# s2.net
KiCad netlist of a schematic drawn in Altium Designer
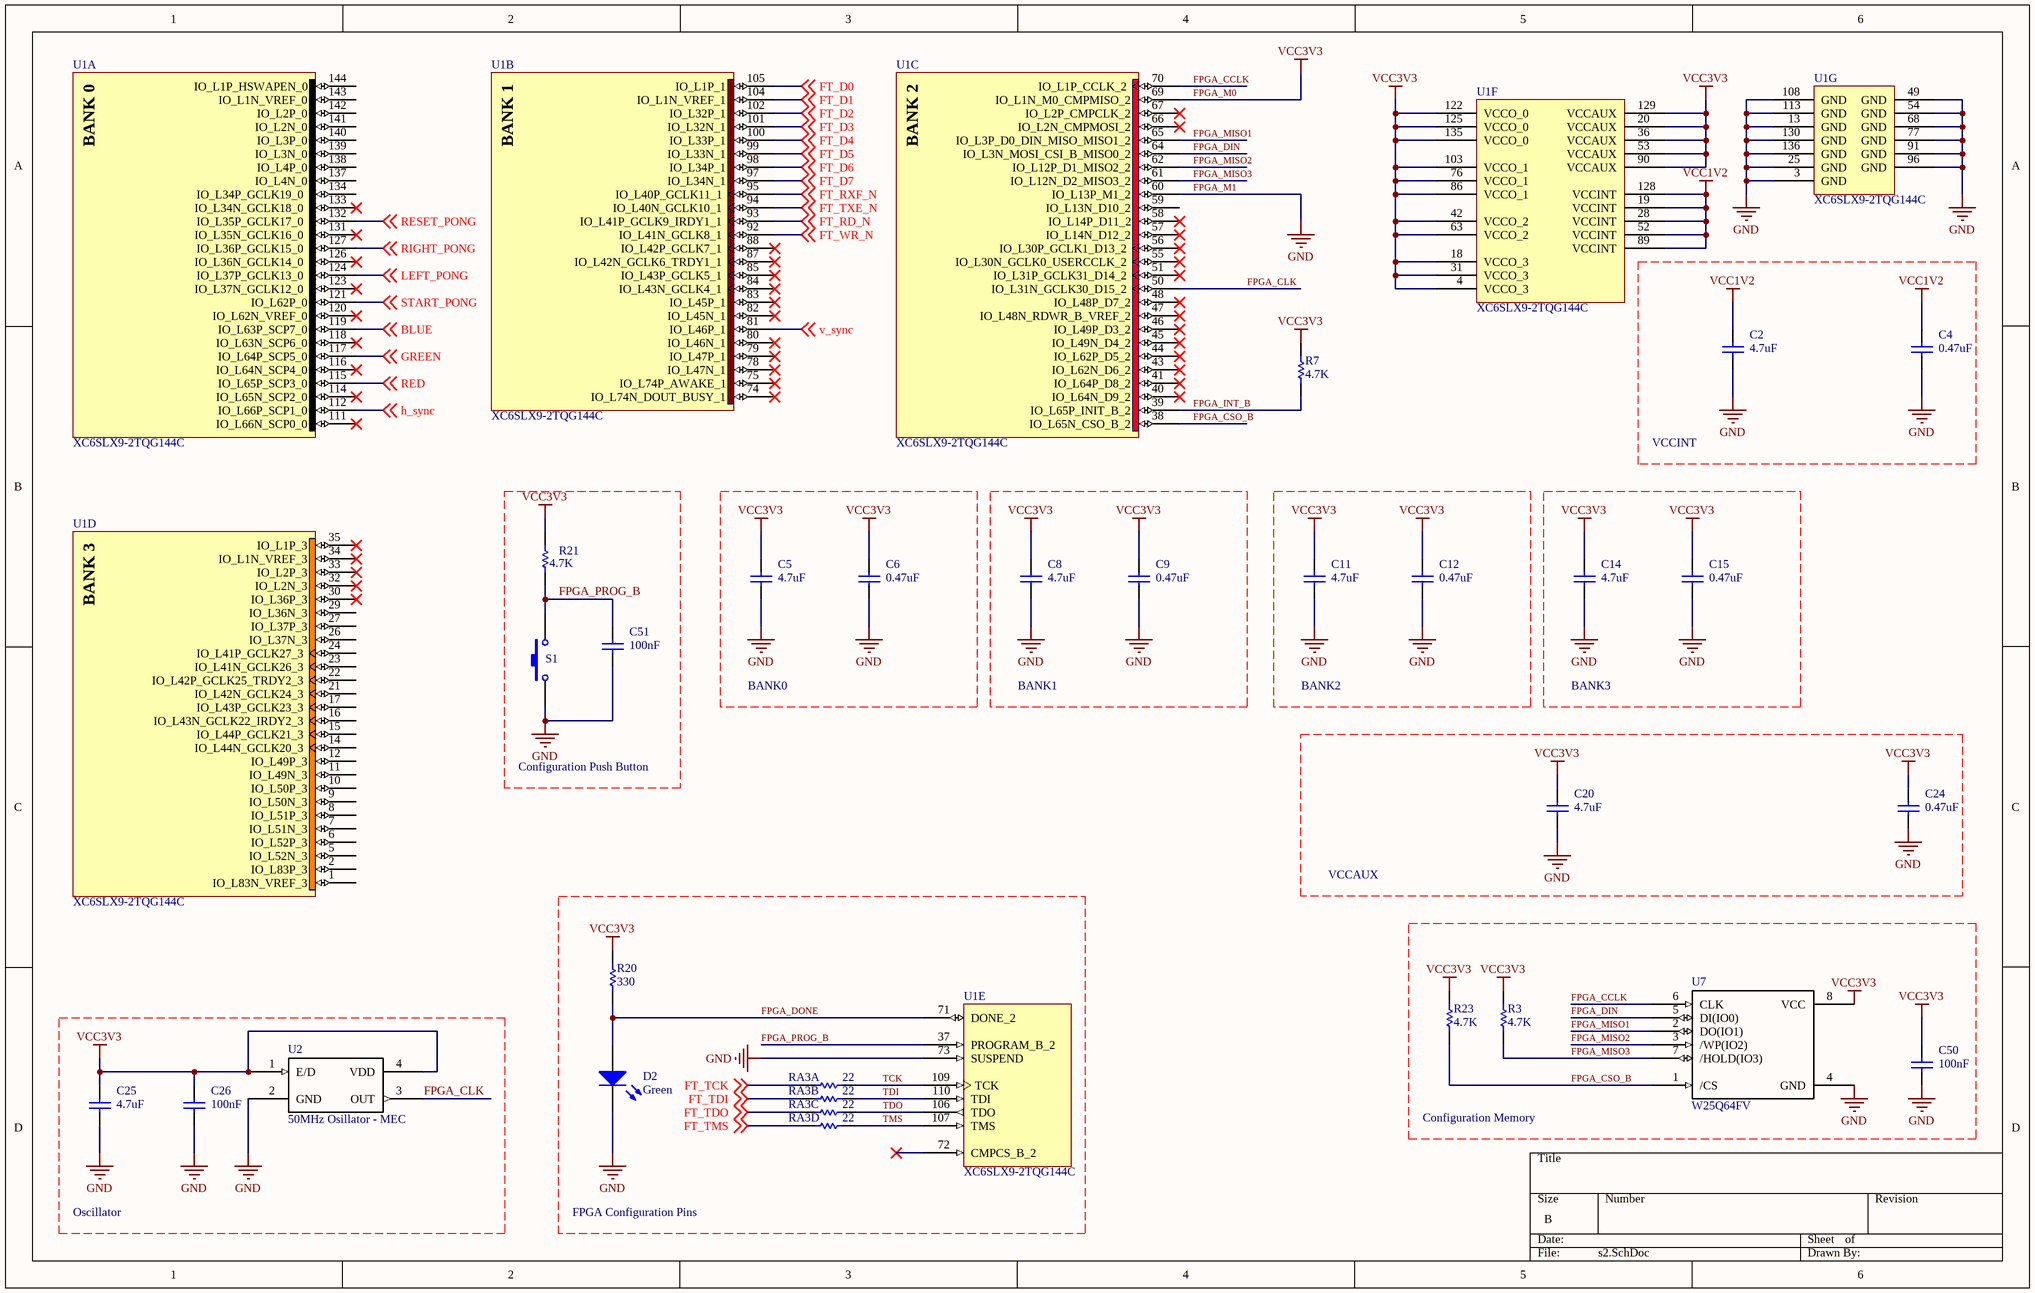
[diagram p0: s2.SchDoc]

(export (version "E")
  (design (tool "Eeschema 10.0.6"))
  (components
    (comp (ref "C2")
      (value "4.7uF")
      (footprint "0805 CAP")
      (description "Capacitor")
      (fields (field (name "Comment") "Cap") (field (name "PUBLISHER") "Altium Limited"))
      (libsource (lib "Miscellaneous Devices") (part "Cap"))
    )
    (comp (ref "C4")
      (value "0.47uF")
      (footprint "0805 CAP")
      (description "Capacitor")
      (fields (field (name "Comment") "Cap") (field (name "PUBLISHER") "Altium Limited"))
      (libsource (lib "Miscellaneous Devices") (part "Cap"))
    )
    (comp (ref "C5")
      (value "4.7uF")
      (footprint "0805 CAP")
      (description "Capacitor")
      (fields (field (name "Comment") "Cap") (field (name "PUBLISHER") "Altium Limited"))
      (libsource (lib "Miscellaneous Devices") (part "Cap"))
    )
    (comp (ref "C6")
      (value "0.47uF")
      (footprint "0805 CAP")
      (description "Capacitor")
      (fields (field (name "Comment") "Cap") (field (name "PUBLISHER") "Altium Limited"))
      (libsource (lib "Miscellaneous Devices") (part "Cap"))
    )
    (comp (ref "C8")
      (value "4.7uF")
      (footprint "0805 CAP")
      (description "Capacitor")
      (fields (field (name "Comment") "Cap") (field (name "PUBLISHER") "Altium Limited"))
      (libsource (lib "Miscellaneous Devices") (part "Cap"))
    )
    (comp (ref "C9")
      (value "0.47uF")
      (footprint "0805 CAP")
      (description "Capacitor")
      (fields (field (name "Comment") "Cap") (field (name "PUBLISHER") "Altium Limited"))
      (libsource (lib "Miscellaneous Devices") (part "Cap"))
    )
    (comp (ref "C11")
      (value "4.7uF")
      (footprint "0805 CAP")
      (description "Capacitor")
      (fields (field (name "Comment") "Cap") (field (name "PUBLISHER") "Altium Limited"))
      (libsource (lib "Miscellaneous Devices") (part "Cap"))
    )
    (comp (ref "C12")
      (value "0.47uF")
      (footprint "0805 CAP")
      (description "Capacitor")
      (fields (field (name "Comment") "Cap") (field (name "PUBLISHER") "Altium Limited"))
      (libsource (lib "Miscellaneous Devices") (part "Cap"))
    )
    (comp (ref "C14")
      (value "4.7uF")
      (footprint "0805 CAP")
      (description "Capacitor")
      (fields (field (name "Comment") "Cap") (field (name "PUBLISHER") "Altium Limited"))
      (libsource (lib "Miscellaneous Devices") (part "Cap"))
    )
    (comp (ref "C15")
      (value "0.47uF")
      (footprint "0805 CAP")
      (description "Capacitor")
      (fields (field (name "Comment") "Cap") (field (name "PUBLISHER") "Altium Limited"))
      (libsource (lib "Miscellaneous Devices") (part "Cap"))
    )
    (comp (ref "C20")
      (value "4.7uF")
      (footprint "0805 CAP")
      (description "Capacitor")
      (fields (field (name "Comment") "Cap") (field (name "PUBLISHER") "Altium Limited"))
      (libsource (lib "Miscellaneous Devices") (part "Cap"))
    )
    (comp (ref "C24")
      (value "0.47uF")
      (footprint "0805 CAP")
      (description "Capacitor")
      (fields (field (name "Comment") "Cap") (field (name "PUBLISHER") "Altium Limited"))
      (libsource (lib "Miscellaneous Devices") (part "Cap"))
    )
    (comp (ref "C25")
      (value "4.7uF")
      (footprint "0805 CAP")
      (description "Capacitor")
      (fields (field (name "Comment") "Cap") (field (name "PUBLISHER") "Altium Limited"))
      (libsource (lib "Miscellaneous Devices") (part "Cap"))
    )
    (comp (ref "C26")
      (value "100nF")
      (footprint "0805 CAP")
      (description "Capacitor")
      (fields (field (name "Comment") "Cap") (field (name "PUBLISHER") "Altium Limited"))
      (libsource (lib "Miscellaneous Devices") (part "Cap"))
    )
    (comp (ref "C50")
      (value "100nF")
      (footprint "0805 CAP")
      (description "Capacitor")
      (fields (field (name "Comment") "Cap") (field (name "PUBLISHER") "Altium Limited"))
      (libsource (lib "Miscellaneous Devices") (part "Cap"))
    )
    (comp (ref "C51")
      (value "100nF")
      (footprint "0805 CAP")
      (description "Capacitor")
      (fields (field (name "Comment") "Cap") (field (name "PUBLISHER") "Altium Limited"))
      (libsource (lib "Miscellaneous Devices") (part "Cap"))
    )
    (comp (ref "D2")
      (value "Green")
      (footprint "0805 LED")
      (description "Typical INFRARED GaAs LED")
      (fields (field (name "PUBLISHER") "Altium Limited"))
      (libsource (lib "Miscellaneous Devices") (part "LED0"))
    )
    (comp (ref "R3")
      (value "4.7K")
      (footprint "0805 RES")
      (description "Resistor")
      (fields (field (name "Comment") "Res1") (field (name "PUBLISHER") "Altium Limited"))
      (libsource (lib "Miscellaneous Devices") (part "Res1"))
    )
    (comp (ref "R7")
      (value "4.7K")
      (footprint "0805 RES")
      (description "Resistor")
      (fields (field (name "Comment") "Res1") (field (name "PUBLISHER") "Altium Limited"))
      (libsource (lib "Miscellaneous Devices") (part "Res1"))
    )
    (comp (ref "R20")
      (value "330")
      (footprint "0805 RES")
      (description "Resistor")
      (fields (field (name "Comment") "Res1") (field (name "PUBLISHER") "Altium Limited"))
      (libsource (lib "Miscellaneous Devices") (part "Res1"))
    )
    (comp (ref "R21")
      (value "4.7K")
      (footprint "0805 RES")
      (description "Resistor")
      (fields (field (name "Comment") "Res1") (field (name "PUBLISHER") "Altium Limited"))
      (libsource (lib "Miscellaneous Devices") (part "Res1"))
    )
    (comp (ref "R23")
      (value "4.7K")
      (footprint "0805 RES")
      (description "Resistor")
      (fields (field (name "Comment") "Res1") (field (name "PUBLISHER") "Altium Limited"))
      (libsource (lib "Miscellaneous Devices") (part "Res1"))
    )
    (comp (ref "RA3A")
      (value "22")
      (footprint "0805 RES")
      (description "Resistor")
      (fields (field (name "Comment") "Res1") (field (name "PUBLISHER") "Altium Limited"))
      (libsource (lib "Miscellaneous Devices") (part "Res1"))
    )
    (comp (ref "RA3B")
      (value "22")
      (footprint "0805 RES")
      (description "Resistor")
      (fields (field (name "Comment") "Res1") (field (name "PUBLISHER") "Altium Limited"))
      (libsource (lib "Miscellaneous Devices") (part "Res1"))
    )
    (comp (ref "RA3C")
      (value "22")
      (footprint "0805 RES")
      (description "Resistor")
      (fields (field (name "Comment") "Res1") (field (name "PUBLISHER") "Altium Limited"))
      (libsource (lib "Miscellaneous Devices") (part "Res1"))
    )
    (comp (ref "RA3D")
      (value "22")
      (footprint "0805 RES")
      (description "Resistor")
      (fields (field (name "Comment") "Res1") (field (name "PUBLISHER") "Altium Limited"))
      (libsource (lib "Miscellaneous Devices") (part "Res1"))
    )
    (comp (ref "S1")
      (value "SW-PB")
      (footprint "Tack Switch")
      (description "Switch")
      (fields (field (name "PUBLISHER") "Altium Limited"))
      (libsource (lib "Miscellaneous Devices") (part "SW-PB"))
    )
    (comp (ref "U1")
      (value "XC6SLX9-2TQG144C")
      (footprint "TQG144_M")
      (libsource (lib "Xilinx Spartan-6") (part "XC6SLX9-2TQG144C"))
    )
    (comp (ref "U2")
      (value "50MHz Osillator - MEC")
      (footprint "50MHz Osillator - MEC")
      (libsource (lib "Schlib1") (part "50MHz Osillator - MEC"))
    )
    (comp (ref "U7")
      (value "W25Q64FV")
      (footprint "SO08 - duplicate")
      (libsource (lib "Schlib1") (part "W25Q64FV"))
    )
  )
  (nets
    (net (code "1") (name "/FPGA_CCLK") (class "Default")
      (node (ref "U1") (pin "70") (pinfunction "IO_L1P_CCLK_2_70") (pintype "bidirectional"))
      (node (ref "U7") (pin "6") (pinfunction "CLK_6") (pintype "input"))
    )
    (net (code "2") (name "/FPGA_CLK") (class "Default")
      (node (ref "U1") (pin "50") (pinfunction "IO_L31N_GCLK30_D15_2_50") (pintype "bidirectional"))
      (node (ref "U2") (pin "3") (pinfunction "OUT_3") (pintype "output"))
    )
    (net (code "3") (name "/FPGA_CSO_B") (class "Default")
      (node (ref "R23") (pin "1") (pinfunction "1_1") (pintype "passive"))
      (node (ref "U1") (pin "38") (pinfunction "IO_L65N_CSO_B_2_38") (pintype "bidirectional"))
      (node (ref "U7") (pin "1") (pinfunction "/CS_1") (pintype "input"))
    )
    (net (code "4") (name "/FPGA_DIN") (class "Default")
      (node (ref "U1") (pin "64") (pinfunction "IO_L3N_MOSI_CSI_B_MISO0_2_64") (pintype "bidirectional"))
      (node (ref "U7") (pin "5") (pinfunction "DI(IO0)_5") (pintype "bidirectional"))
    )
    (net (code "5") (name "/FPGA_DONE") (class "Default")
      (node (ref "D2") (pin "1") (pinfunction "A_1") (pintype "passive"))
      (node (ref "R20") (pin "1") (pinfunction "1_1") (pintype "passive"))
      (node (ref "U1") (pin "71") (pinfunction "DONE_2_71") (pintype "bidirectional"))
    )
    (net (code "6") (name "/FPGA_INT_B") (class "Default")
      (node (ref "R7") (pin "1") (pinfunction "1_1") (pintype "passive"))
      (node (ref "U1") (pin "39") (pinfunction "IO_L65P_INIT_B_2_39") (pintype "bidirectional"))
    )
    (net (code "7") (name "/FPGA_MISO1") (class "Default")
      (node (ref "U1") (pin "65") (pinfunction "IO_L3P_D0_DIN_MISO_MISO1_2_65") (pintype "bidirectional"))
      (node (ref "U7") (pin "2") (pinfunction "DO(IO1)_2") (pintype "bidirectional"))
    )
    (net (code "8") (name "/FPGA_MISO2") (class "Default")
      (node (ref "U1") (pin "62") (pinfunction "IO_L12P_D1_MISO2_2_62") (pintype "bidirectional"))
      (node (ref "U7") (pin "3") (pinfunction "/WP(IO2)_3") (pintype "input"))
    )
    (net (code "9") (name "/FPGA_MISO3") (class "Default")
      (node (ref "R3") (pin "1") (pinfunction "1_1") (pintype "passive"))
      (node (ref "U1") (pin "61") (pinfunction "IO_L12N_D2_MISO3_2_61") (pintype "bidirectional"))
      (node (ref "U7") (pin "7") (pinfunction "/HOLD(IO3)_7") (pintype "bidirectional"))
    )
    (net (code "10") (name "/FPGA_PROG_B") (class "Default")
      (node (ref "C51") (pin "2") (pinfunction "2_2") (pintype "passive"))
      (node (ref "R21") (pin "1") (pinfunction "1_1") (pintype "passive"))
      (node (ref "S1") (pin "2") (pinfunction "2_2") (pintype "passive"))
      (node (ref "U1") (pin "37") (pinfunction "PROGRAM_B_2_37") (pintype "input"))
    )
    (net (code "11") (name "/TCK") (class "Default")
      (node (ref "RA3A") (pin "1") (pinfunction "1_1") (pintype "passive"))
      (node (ref "U1") (pin "109") (pinfunction "TCK_109") (pintype "input"))
    )
    (net (code "12") (name "/TDI") (class "Default")
      (node (ref "RA3B") (pin "1") (pinfunction "1_1") (pintype "passive"))
      (node (ref "U1") (pin "110") (pinfunction "TDI_110") (pintype "input"))
    )
    (net (code "13") (name "/TDO") (class "Default")
      (node (ref "RA3C") (pin "1") (pinfunction "1_1") (pintype "passive"))
      (node (ref "U1") (pin "106") (pinfunction "TDO_106") (pintype "output"))
    )
    (net (code "14") (name "/TMS") (class "Default")
      (node (ref "RA3D") (pin "1") (pinfunction "1_1") (pintype "passive"))
      (node (ref "U1") (pin "107") (pinfunction "TMS_107") (pintype "input"))
    )
    (net (code "15") (name "BLUE") (class "Default")
      (node (ref "U1") (pin "119") (pinfunction "IO_L63P_SCP7_0_119") (pintype "bidirectional"))
    )
    (net (code "16") (name "FT_D0") (class "Default")
      (node (ref "U1") (pin "105") (pinfunction "IO_L1P_1_105") (pintype "bidirectional"))
    )
    (net (code "17") (name "FT_D1") (class "Default")
      (node (ref "U1") (pin "104") (pinfunction "IO_L1N_VREF_1_104") (pintype "bidirectional"))
    )
    (net (code "18") (name "FT_D2") (class "Default")
      (node (ref "U1") (pin "102") (pinfunction "IO_L32P_1_102") (pintype "bidirectional"))
    )
    (net (code "19") (name "FT_D3") (class "Default")
      (node (ref "U1") (pin "101") (pinfunction "IO_L32N_1_101") (pintype "bidirectional"))
    )
    (net (code "20") (name "FT_D4") (class "Default")
      (node (ref "U1") (pin "100") (pinfunction "IO_L33P_1_100") (pintype "bidirectional"))
    )
    (net (code "21") (name "FT_D5") (class "Default")
      (node (ref "U1") (pin "99") (pinfunction "IO_L33N_1_99") (pintype "bidirectional"))
    )
    (net (code "22") (name "FT_D6") (class "Default")
      (node (ref "U1") (pin "98") (pinfunction "IO_L34P_1_98") (pintype "bidirectional"))
    )
    (net (code "23") (name "FT_D7") (class "Default")
      (node (ref "U1") (pin "97") (pinfunction "IO_L34N_1_97") (pintype "bidirectional"))
    )
    (net (code "24") (name "FT_RD_N") (class "Default")
      (node (ref "U1") (pin "93") (pinfunction "IO_L41P_GCLK9_IRDY1_1_93") (pintype "bidirectional"))
    )
    (net (code "25") (name "FT_RXF_N") (class "Default")
      (node (ref "U1") (pin "95") (pinfunction "IO_L40P_GCLK11_1_95") (pintype "bidirectional"))
    )
    (net (code "26") (name "FT_TCK") (class "Default")
      (node (ref "RA3A") (pin "2") (pinfunction "2_2") (pintype "passive"))
    )
    (net (code "27") (name "FT_TDI") (class "Default")
      (node (ref "RA3B") (pin "2") (pinfunction "2_2") (pintype "passive"))
    )
    (net (code "28") (name "FT_TDO") (class "Default")
      (node (ref "RA3C") (pin "2") (pinfunction "2_2") (pintype "passive"))
    )
    (net (code "29") (name "FT_TMS") (class "Default")
      (node (ref "RA3D") (pin "2") (pinfunction "2_2") (pintype "passive"))
    )
    (net (code "30") (name "FT_TXE_N") (class "Default")
      (node (ref "U1") (pin "94") (pinfunction "IO_L40N_GCLK10_1_94") (pintype "bidirectional"))
    )
    (net (code "31") (name "FT_WR_N") (class "Default")
      (node (ref "U1") (pin "92") (pinfunction "IO_L41N_GCLK8_1_92") (pintype "bidirectional"))
    )
    (net (code "32") (name "GND") (class "Default")
      (node (ref "C11") (pin "1") (pinfunction "1_1") (pintype "passive"))
      (node (ref "C12") (pin "1") (pinfunction "1_1") (pintype "passive"))
      (node (ref "C14") (pin "1") (pinfunction "1_1") (pintype "passive"))
      (node (ref "C15") (pin "1") (pinfunction "1_1") (pintype "passive"))
      (node (ref "C2") (pin "1") (pinfunction "1_1") (pintype "passive"))
      (node (ref "C20") (pin "1") (pinfunction "1_1") (pintype "passive"))
      (node (ref "C24") (pin "1") (pinfunction "1_1") (pintype "passive"))
      (node (ref "C25") (pin "1") (pinfunction "1_1") (pintype "passive"))
      (node (ref "C26") (pin "1") (pinfunction "1_1") (pintype "passive"))
      (node (ref "C4") (pin "1") (pinfunction "1_1") (pintype "passive"))
      (node (ref "C5") (pin "1") (pinfunction "1_1") (pintype "passive"))
      (node (ref "C50") (pin "1") (pinfunction "1_1") (pintype "passive"))
      (node (ref "C51") (pin "1") (pinfunction "1_1") (pintype "passive"))
      (node (ref "C6") (pin "1") (pinfunction "1_1") (pintype "passive"))
      (node (ref "C8") (pin "1") (pinfunction "1_1") (pintype "passive"))
      (node (ref "C9") (pin "1") (pinfunction "1_1") (pintype "passive"))
      (node (ref "D2") (pin "2") (pinfunction "K_2") (pintype "passive"))
      (node (ref "S1") (pin "1") (pinfunction "1_1") (pintype "passive"))
      (node (ref "U1") (pin "108") (pinfunction "GND_108") (pintype "power_in"))
      (node (ref "U1") (pin "113") (pinfunction "GND_113") (pintype "power_in"))
      (node (ref "U1") (pin "13") (pinfunction "GND_13") (pintype "power_in"))
      (node (ref "U1") (pin "130") (pinfunction "GND_130") (pintype "power_in"))
      (node (ref "U1") (pin "136") (pinfunction "GND_136") (pintype "power_in"))
      (node (ref "U1") (pin "25") (pinfunction "GND_25") (pintype "power_in"))
      (node (ref "U1") (pin "3") (pinfunction "GND_3") (pintype "power_in"))
      (node (ref "U1") (pin "49") (pinfunction "GND_49") (pintype "power_in"))
      (node (ref "U1") (pin "54") (pinfunction "GND_54") (pintype "power_in"))
      (node (ref "U1") (pin "60") (pinfunction "IO_L13P_M1_2_60") (pintype "bidirectional"))
      (node (ref "U1") (pin "68") (pinfunction "GND_68") (pintype "power_in"))
      (node (ref "U1") (pin "73") (pinfunction "SUSPEND_73") (pintype "input"))
      (node (ref "U1") (pin "77") (pinfunction "GND_77") (pintype "power_in"))
      (node (ref "U1") (pin "91") (pinfunction "GND_91") (pintype "power_in"))
      (node (ref "U1") (pin "96") (pinfunction "GND_96") (pintype "power_in"))
      (node (ref "U2") (pin "2") (pinfunction "GND_2") (pintype "passive"))
      (node (ref "U7") (pin "4") (pinfunction "GND_4") (pintype "passive"))
    )
    (net (code "33") (name "GREEN") (class "Default")
      (node (ref "U1") (pin "117") (pinfunction "IO_L64P_SCP5_0_117") (pintype "bidirectional"))
    )
    (net (code "34") (name "LEFT_PONG") (class "Default")
      (node (ref "U1") (pin "124") (pinfunction "IO_L37P_GCLK13_0_124") (pintype "bidirectional"))
    )
    (net (code "35") (name "RED") (class "Default")
      (node (ref "U1") (pin "115") (pinfunction "IO_L65P_SCP3_0_115") (pintype "bidirectional"))
    )
    (net (code "36") (name "RESET_PONG") (class "Default")
      (node (ref "U1") (pin "132") (pinfunction "IO_L35P_GCLK17_0_132") (pintype "bidirectional"))
    )
    (net (code "37") (name "RIGHT_PONG") (class "Default")
      (node (ref "U1") (pin "127") (pinfunction "IO_L36P_GCLK15_0_127") (pintype "bidirectional"))
    )
    (net (code "38") (name "START_PONG") (class "Default")
      (node (ref "U1") (pin "121") (pinfunction "IO_L62P_0_121") (pintype "bidirectional"))
    )
    (net (code "39") (name "VCC1V2") (class "Default")
      (node (ref "C2") (pin "2") (pinfunction "2_2") (pintype "passive"))
      (node (ref "C4") (pin "2") (pinfunction "2_2") (pintype "passive"))
      (node (ref "U1") (pin "128") (pinfunction "VCCINT_128") (pintype "power_in"))
      (node (ref "U1") (pin "19") (pinfunction "VCCINT_19") (pintype "power_in"))
      (node (ref "U1") (pin "28") (pinfunction "VCCINT_28") (pintype "power_in"))
      (node (ref "U1") (pin "52") (pinfunction "VCCINT_52") (pintype "power_in"))
      (node (ref "U1") (pin "89") (pinfunction "VCCINT_89") (pintype "power_in"))
    )
    (net (code "40") (name "VCC3V3") (class "Default")
      (node (ref "C11") (pin "2") (pinfunction "2_2") (pintype "passive"))
      (node (ref "C12") (pin "2") (pinfunction "2_2") (pintype "passive"))
      (node (ref "C14") (pin "2") (pinfunction "2_2") (pintype "passive"))
      (node (ref "C15") (pin "2") (pinfunction "2_2") (pintype "passive"))
      (node (ref "C20") (pin "2") (pinfunction "2_2") (pintype "passive"))
      (node (ref "C24") (pin "2") (pinfunction "2_2") (pintype "passive"))
      (node (ref "C25") (pin "2") (pinfunction "2_2") (pintype "passive"))
      (node (ref "C26") (pin "2") (pinfunction "2_2") (pintype "passive"))
      (node (ref "C5") (pin "2") (pinfunction "2_2") (pintype "passive"))
      (node (ref "C50") (pin "2") (pinfunction "2_2") (pintype "passive"))
      (node (ref "C6") (pin "2") (pinfunction "2_2") (pintype "passive"))
      (node (ref "C8") (pin "2") (pinfunction "2_2") (pintype "passive"))
      (node (ref "C9") (pin "2") (pinfunction "2_2") (pintype "passive"))
      (node (ref "R20") (pin "2") (pinfunction "2_2") (pintype "passive"))
      (node (ref "R21") (pin "2") (pinfunction "2_2") (pintype "passive"))
      (node (ref "R23") (pin "2") (pinfunction "2_2") (pintype "passive"))
      (node (ref "R3") (pin "2") (pinfunction "2_2") (pintype "passive"))
      (node (ref "R7") (pin "2") (pinfunction "2_2") (pintype "passive"))
      (node (ref "U1") (pin "103") (pinfunction "VCCO_1_103") (pintype "power_in"))
      (node (ref "U1") (pin "122") (pinfunction "VCCO_0_122") (pintype "power_in"))
      (node (ref "U1") (pin "125") (pinfunction "VCCO_0_125") (pintype "power_in"))
      (node (ref "U1") (pin "129") (pinfunction "VCCAUX_129") (pintype "power_in"))
      (node (ref "U1") (pin "135") (pinfunction "VCCO_0_135") (pintype "power_in"))
      (node (ref "U1") (pin "18") (pinfunction "VCCO_3_18") (pintype "power_in"))
      (node (ref "U1") (pin "20") (pinfunction "VCCAUX_20") (pintype "power_in"))
      (node (ref "U1") (pin "31") (pinfunction "VCCO_3_31") (pintype "power_in"))
      (node (ref "U1") (pin "36") (pinfunction "VCCAUX_36") (pintype "power_in"))
      (node (ref "U1") (pin "4") (pinfunction "VCCO_3_4") (pintype "power_in"))
      (node (ref "U1") (pin "42") (pinfunction "VCCO_2_42") (pintype "power_in"))
      (node (ref "U1") (pin "53") (pinfunction "VCCAUX_53") (pintype "power_in"))
      (node (ref "U1") (pin "63") (pinfunction "VCCO_2_63") (pintype "power_in"))
      (node (ref "U1") (pin "69") (pinfunction "IO_L1N_M0_CMPMISO_2_69") (pintype "bidirectional"))
      (node (ref "U1") (pin "76") (pinfunction "VCCO_1_76") (pintype "power_in"))
      (node (ref "U1") (pin "86") (pinfunction "VCCO_1_86") (pintype "power_in"))
      (node (ref "U1") (pin "90") (pinfunction "VCCAUX_90") (pintype "power_in"))
      (node (ref "U2") (pin "1") (pinfunction "E/D_1") (pintype "input"))
      (node (ref "U2") (pin "4") (pinfunction "VDD_4") (pintype "passive"))
      (node (ref "U7") (pin "8") (pinfunction "VCC_8") (pintype "power_in"))
    )
    (net (code "41") (name "h_sync") (class "Default")
      (node (ref "U1") (pin "112") (pinfunction "IO_L66P_SCP1_0_112") (pintype "bidirectional"))
    )
    (net (code "42") (name "unconnected-(U1A-IO_L1N_VREF_0-Pad143)") (class "Default")
      (node (ref "U1") (pin "143") (pinfunction "IO_L1N_VREF_0_143") (pintype "bidirectional"))
    )
    (net (code "43") (name "unconnected-(U1A-IO_L1P_HSWAPEN_0-Pad144)") (class "Default")
      (node (ref "U1") (pin "144") (pinfunction "IO_L1P_HSWAPEN_0_144") (pintype "bidirectional"))
    )
    (net (code "44") (name "unconnected-(U1A-IO_L2N_0-Pad141)") (class "Default")
      (node (ref "U1") (pin "141") (pinfunction "IO_L2N_0_141") (pintype "bidirectional"))
    )
    (net (code "45") (name "unconnected-(U1A-IO_L2P_0-Pad142)") (class "Default")
      (node (ref "U1") (pin "142") (pinfunction "IO_L2P_0_142") (pintype "bidirectional"))
    )
    (net (code "46") (name "unconnected-(U1A-IO_L3N_0-Pad139)") (class "Default")
      (node (ref "U1") (pin "139") (pinfunction "IO_L3N_0_139") (pintype "bidirectional"))
    )
    (net (code "47") (name "unconnected-(U1A-IO_L3P_0-Pad140)") (class "Default")
      (node (ref "U1") (pin "140") (pinfunction "IO_L3P_0_140") (pintype "bidirectional"))
    )
    (net (code "48") (name "unconnected-(U1A-IO_L4N_0-Pad137)") (class "Default")
      (node (ref "U1") (pin "137") (pinfunction "IO_L4N_0_137") (pintype "bidirectional"))
    )
    (net (code "49") (name "unconnected-(U1A-IO_L4P_0-Pad138)") (class "Default")
      (node (ref "U1") (pin "138") (pinfunction "IO_L4P_0_138") (pintype "bidirectional"))
    )
    (net (code "50") (name "unconnected-(U1A-IO_L34N_GCLK18_0-Pad133)") (class "Default")
      (node (ref "U1") (pin "133") (pinfunction "IO_L34N_GCLK18_0_133") (pintype "bidirectional+no_connect"))
    )
    (net (code "51") (name "unconnected-(U1A-IO_L34P_GCLK19_0-Pad134)") (class "Default")
      (node (ref "U1") (pin "134") (pinfunction "IO_L34P_GCLK19_0_134") (pintype "bidirectional"))
    )
    (net (code "52") (name "unconnected-(U1A-IO_L35N_GCLK16_0-Pad131)") (class "Default")
      (node (ref "U1") (pin "131") (pinfunction "IO_L35N_GCLK16_0_131") (pintype "bidirectional+no_connect"))
    )
    (net (code "53") (name "unconnected-(U1A-IO_L36N_GCLK14_0-Pad126)") (class "Default")
      (node (ref "U1") (pin "126") (pinfunction "IO_L36N_GCLK14_0_126") (pintype "bidirectional+no_connect"))
    )
    (net (code "54") (name "unconnected-(U1A-IO_L37N_GCLK12_0-Pad123)") (class "Default")
      (node (ref "U1") (pin "123") (pinfunction "IO_L37N_GCLK12_0_123") (pintype "bidirectional+no_connect"))
    )
    (net (code "55") (name "unconnected-(U1A-IO_L62N_VREF_0-Pad120)") (class "Default")
      (node (ref "U1") (pin "120") (pinfunction "IO_L62N_VREF_0_120") (pintype "bidirectional+no_connect"))
    )
    (net (code "56") (name "unconnected-(U1A-IO_L63N_SCP6_0-Pad118)") (class "Default")
      (node (ref "U1") (pin "118") (pinfunction "IO_L63N_SCP6_0_118") (pintype "bidirectional+no_connect"))
    )
    (net (code "57") (name "unconnected-(U1A-IO_L64N_SCP4_0-Pad116)") (class "Default")
      (node (ref "U1") (pin "116") (pinfunction "IO_L64N_SCP4_0_116") (pintype "bidirectional+no_connect"))
    )
    (net (code "58") (name "unconnected-(U1A-IO_L65N_SCP2_0-Pad114)") (class "Default")
      (node (ref "U1") (pin "114") (pinfunction "IO_L65N_SCP2_0_114") (pintype "bidirectional+no_connect"))
    )
    (net (code "59") (name "unconnected-(U1A-IO_L66N_SCP0_0-Pad111)") (class "Default")
      (node (ref "U1") (pin "111") (pinfunction "IO_L66N_SCP0_0_111") (pintype "bidirectional+no_connect"))
    )
    (net (code "60") (name "unconnected-(U1B-IO_L42N_GCLK6_TRDY1_1-Pad87)") (class "Default")
      (node (ref "U1") (pin "87") (pinfunction "IO_L42N_GCLK6_TRDY1_1_87") (pintype "bidirectional+no_connect"))
    )
    (net (code "61") (name "unconnected-(U1B-IO_L42P_GCLK7_1-Pad88)") (class "Default")
      (node (ref "U1") (pin "88") (pinfunction "IO_L42P_GCLK7_1_88") (pintype "bidirectional+no_connect"))
    )
    (net (code "62") (name "unconnected-(U1B-IO_L43N_GCLK4_1-Pad84)") (class "Default")
      (node (ref "U1") (pin "84") (pinfunction "IO_L43N_GCLK4_1_84") (pintype "bidirectional+no_connect"))
    )
    (net (code "63") (name "unconnected-(U1B-IO_L43P_GCLK5_1-Pad85)") (class "Default")
      (node (ref "U1") (pin "85") (pinfunction "IO_L43P_GCLK5_1_85") (pintype "bidirectional+no_connect"))
    )
    (net (code "64") (name "unconnected-(U1B-IO_L45N_1-Pad82)") (class "Default")
      (node (ref "U1") (pin "82") (pinfunction "IO_L45N_1_82") (pintype "bidirectional+no_connect"))
    )
    (net (code "65") (name "unconnected-(U1B-IO_L45P_1-Pad83)") (class "Default")
      (node (ref "U1") (pin "83") (pinfunction "IO_L45P_1_83") (pintype "bidirectional+no_connect"))
    )
    (net (code "66") (name "unconnected-(U1B-IO_L46N_1-Pad80)") (class "Default")
      (node (ref "U1") (pin "80") (pinfunction "IO_L46N_1_80") (pintype "bidirectional+no_connect"))
    )
    (net (code "67") (name "unconnected-(U1B-IO_L47N_1-Pad78)") (class "Default")
      (node (ref "U1") (pin "78") (pinfunction "IO_L47N_1_78") (pintype "bidirectional+no_connect"))
    )
    (net (code "68") (name "unconnected-(U1B-IO_L47P_1-Pad79)") (class "Default")
      (node (ref "U1") (pin "79") (pinfunction "IO_L47P_1_79") (pintype "bidirectional+no_connect"))
    )
    (net (code "69") (name "unconnected-(U1B-IO_L74N_DOUT_BUSY_1-Pad74)") (class "Default")
      (node (ref "U1") (pin "74") (pinfunction "IO_L74N_DOUT_BUSY_1_74") (pintype "bidirectional+no_connect"))
    )
    (net (code "70") (name "unconnected-(U1B-IO_L74P_AWAKE_1-Pad75)") (class "Default")
      (node (ref "U1") (pin "75") (pinfunction "IO_L74P_AWAKE_1_75") (pintype "bidirectional+no_connect"))
    )
    (net (code "71") (name "unconnected-(U1C-IO_L2N_CMPMOSI_2-Pad66)") (class "Default")
      (node (ref "U1") (pin "66") (pinfunction "IO_L2N_CMPMOSI_2_66") (pintype "bidirectional+no_connect"))
    )
    (net (code "72") (name "unconnected-(U1C-IO_L2P_CMPCLK_2-Pad67)") (class "Default")
      (node (ref "U1") (pin "67") (pinfunction "IO_L2P_CMPCLK_2_67") (pintype "bidirectional+no_connect"))
    )
    (net (code "73") (name "unconnected-(U1C-IO_L13N_D10_2-Pad59)") (class "Default")
      (node (ref "U1") (pin "59") (pinfunction "IO_L13N_D10_2_59") (pintype "bidirectional"))
    )
    (net (code "74") (name "unconnected-(U1C-IO_L14N_D12_2-Pad57)") (class "Default")
      (node (ref "U1") (pin "57") (pinfunction "IO_L14N_D12_2_57") (pintype "bidirectional+no_connect"))
    )
    (net (code "75") (name "unconnected-(U1C-IO_L14P_D11_2-Pad58)") (class "Default")
      (node (ref "U1") (pin "58") (pinfunction "IO_L14P_D11_2_58") (pintype "bidirectional+no_connect"))
    )
    (net (code "76") (name "unconnected-(U1C-IO_L30N_GCLK0_USERCCLK_2-Pad55)") (class "Default")
      (node (ref "U1") (pin "55") (pinfunction "IO_L30N_GCLK0_USERCCLK_2_55") (pintype "bidirectional+no_connect"))
    )
    (net (code "77") (name "unconnected-(U1C-IO_L30P_GCLK1_D13_2-Pad56)") (class "Default")
      (node (ref "U1") (pin "56") (pinfunction "IO_L30P_GCLK1_D13_2_56") (pintype "bidirectional+no_connect"))
    )
    (net (code "78") (name "unconnected-(U1C-IO_L31P_GCLK31_D14_2-Pad51)") (class "Default")
      (node (ref "U1") (pin "51") (pinfunction "IO_L31P_GCLK31_D14_2_51") (pintype "bidirectional+no_connect"))
    )
    (net (code "79") (name "unconnected-(U1C-IO_L48N_RDWR_B_VREF_2-Pad47)") (class "Default")
      (node (ref "U1") (pin "47") (pinfunction "IO_L48N_RDWR_B_VREF_2_47") (pintype "bidirectional+no_connect"))
    )
    (net (code "80") (name "unconnected-(U1C-IO_L48P_D7_2-Pad48)") (class "Default")
      (node (ref "U1") (pin "48") (pinfunction "IO_L48P_D7_2_48") (pintype "bidirectional+no_connect"))
    )
    (net (code "81") (name "unconnected-(U1C-IO_L49N_D4_2-Pad45)") (class "Default")
      (node (ref "U1") (pin "45") (pinfunction "IO_L49N_D4_2_45") (pintype "bidirectional+no_connect"))
    )
    (net (code "82") (name "unconnected-(U1C-IO_L49P_D3_2-Pad46)") (class "Default")
      (node (ref "U1") (pin "46") (pinfunction "IO_L49P_D3_2_46") (pintype "bidirectional+no_connect"))
    )
    (net (code "83") (name "unconnected-(U1C-IO_L62N_D6_2-Pad43)") (class "Default")
      (node (ref "U1") (pin "43") (pinfunction "IO_L62N_D6_2_43") (pintype "bidirectional+no_connect"))
    )
    (net (code "84") (name "unconnected-(U1C-IO_L62P_D5_2-Pad44)") (class "Default")
      (node (ref "U1") (pin "44") (pinfunction "IO_L62P_D5_2_44") (pintype "bidirectional+no_connect"))
    )
    (net (code "85") (name "unconnected-(U1C-IO_L64N_D9_2-Pad40)") (class "Default")
      (node (ref "U1") (pin "40") (pinfunction "IO_L64N_D9_2_40") (pintype "bidirectional+no_connect"))
    )
    (net (code "86") (name "unconnected-(U1C-IO_L64P_D8_2-Pad41)") (class "Default")
      (node (ref "U1") (pin "41") (pinfunction "IO_L64P_D8_2_41") (pintype "bidirectional+no_connect"))
    )
    (net (code "87") (name "unconnected-(U1D-IO_L1N_VREF_3-Pad34)") (class "Default")
      (node (ref "U1") (pin "34") (pinfunction "IO_L1N_VREF_3_34") (pintype "bidirectional+no_connect"))
    )
    (net (code "88") (name "unconnected-(U1D-IO_L1P_3-Pad35)") (class "Default")
      (node (ref "U1") (pin "35") (pinfunction "IO_L1P_3_35") (pintype "bidirectional+no_connect"))
    )
    (net (code "89") (name "unconnected-(U1D-IO_L2N_3-Pad32)") (class "Default")
      (node (ref "U1") (pin "32") (pinfunction "IO_L2N_3_32") (pintype "bidirectional+no_connect"))
    )
    (net (code "90") (name "unconnected-(U1D-IO_L2P_3-Pad33)") (class "Default")
      (node (ref "U1") (pin "33") (pinfunction "IO_L2P_3_33") (pintype "bidirectional+no_connect"))
    )
    (net (code "91") (name "unconnected-(U1D-IO_L36N_3-Pad29)") (class "Default")
      (node (ref "U1") (pin "29") (pinfunction "IO_L36N_3_29") (pintype "bidirectional"))
    )
    (net (code "92") (name "unconnected-(U1D-IO_L36P_3-Pad30)") (class "Default")
      (node (ref "U1") (pin "30") (pinfunction "IO_L36P_3_30") (pintype "bidirectional+no_connect"))
    )
    (net (code "93") (name "unconnected-(U1D-IO_L37N_3-Pad26)") (class "Default")
      (node (ref "U1") (pin "26") (pinfunction "IO_L37N_3_26") (pintype "bidirectional"))
    )
    (net (code "94") (name "unconnected-(U1D-IO_L37P_3-Pad27)") (class "Default")
      (node (ref "U1") (pin "27") (pinfunction "IO_L37P_3_27") (pintype "bidirectional"))
    )
    (net (code "95") (name "unconnected-(U1D-IO_L41N_GCLK26_3-Pad23)") (class "Default")
      (node (ref "U1") (pin "23") (pinfunction "IO_L41N_GCLK26_3_23") (pintype "bidirectional"))
    )
    (net (code "96") (name "unconnected-(U1D-IO_L41P_GCLK27_3-Pad24)") (class "Default")
      (node (ref "U1") (pin "24") (pinfunction "IO_L41P_GCLK27_3_24") (pintype "bidirectional"))
    )
    (net (code "97") (name "unconnected-(U1D-IO_L42N_GCLK24_3-Pad21)") (class "Default")
      (node (ref "U1") (pin "21") (pinfunction "IO_L42N_GCLK24_3_21") (pintype "bidirectional"))
    )
    (net (code "98") (name "unconnected-(U1D-IO_L42P_GCLK25_TRDY2_3-Pad22)") (class "Default")
      (node (ref "U1") (pin "22") (pinfunction "IO_L42P_GCLK25_TRDY2_3_22") (pintype "bidirectional"))
    )
    (net (code "99") (name "unconnected-(U1D-IO_L43N_GCLK22_IRDY2_3-Pad16)") (class "Default")
      (node (ref "U1") (pin "16") (pinfunction "IO_L43N_GCLK22_IRDY2_3_16") (pintype "bidirectional"))
    )
    (net (code "100") (name "unconnected-(U1D-IO_L43P_GCLK23_3-Pad17)") (class "Default")
      (node (ref "U1") (pin "17") (pinfunction "IO_L43P_GCLK23_3_17") (pintype "bidirectional"))
    )
    (net (code "101") (name "unconnected-(U1D-IO_L44N_GCLK20_3-Pad14)") (class "Default")
      (node (ref "U1") (pin "14") (pinfunction "IO_L44N_GCLK20_3_14") (pintype "bidirectional"))
    )
    (net (code "102") (name "unconnected-(U1D-IO_L44P_GCLK21_3-Pad15)") (class "Default")
      (node (ref "U1") (pin "15") (pinfunction "IO_L44P_GCLK21_3_15") (pintype "bidirectional"))
    )
    (net (code "103") (name "unconnected-(U1D-IO_L49N_3-Pad11)") (class "Default")
      (node (ref "U1") (pin "11") (pinfunction "IO_L49N_3_11") (pintype "bidirectional"))
    )
    (net (code "104") (name "unconnected-(U1D-IO_L49P_3-Pad12)") (class "Default")
      (node (ref "U1") (pin "12") (pinfunction "IO_L49P_3_12") (pintype "bidirectional"))
    )
    (net (code "105") (name "unconnected-(U1D-IO_L50N_3-Pad9)") (class "Default")
      (node (ref "U1") (pin "9") (pinfunction "IO_L50N_3_9") (pintype "bidirectional"))
    )
    (net (code "106") (name "unconnected-(U1D-IO_L50P_3-Pad10)") (class "Default")
      (node (ref "U1") (pin "10") (pinfunction "IO_L50P_3_10") (pintype "bidirectional"))
    )
    (net (code "107") (name "unconnected-(U1D-IO_L51N_3-Pad7)") (class "Default")
      (node (ref "U1") (pin "7") (pinfunction "IO_L51N_3_7") (pintype "bidirectional"))
    )
    (net (code "108") (name "unconnected-(U1D-IO_L51P_3-Pad8)") (class "Default")
      (node (ref "U1") (pin "8") (pinfunction "IO_L51P_3_8") (pintype "bidirectional"))
    )
    (net (code "109") (name "unconnected-(U1D-IO_L52N_3-Pad5)") (class "Default")
      (node (ref "U1") (pin "5") (pinfunction "IO_L52N_3_5") (pintype "bidirectional"))
    )
    (net (code "110") (name "unconnected-(U1D-IO_L52P_3-Pad6)") (class "Default")
      (node (ref "U1") (pin "6") (pinfunction "IO_L52P_3_6") (pintype "bidirectional"))
    )
    (net (code "111") (name "unconnected-(U1D-IO_L83N_VREF_3-Pad1)") (class "Default")
      (node (ref "U1") (pin "1") (pinfunction "IO_L83N_VREF_3_1") (pintype "bidirectional"))
    )
    (net (code "112") (name "unconnected-(U1D-IO_L83P_3-Pad2)") (class "Default")
      (node (ref "U1") (pin "2") (pinfunction "IO_L83P_3_2") (pintype "bidirectional"))
    )
    (net (code "113") (name "unconnected-(U1E-CMPCS_B_2-Pad72)") (class "Default")
      (node (ref "U1") (pin "72") (pinfunction "CMPCS_B_2_72") (pintype "input+no_connect"))
    )
    (net (code "114") (name "v_sync") (class "Default")
      (node (ref "U1") (pin "81") (pinfunction "IO_L46P_1_81") (pintype "bidirectional"))
    )
  )
)
